# ESP32.net
KiCad netlist of a schematic drawn in Altium Designer
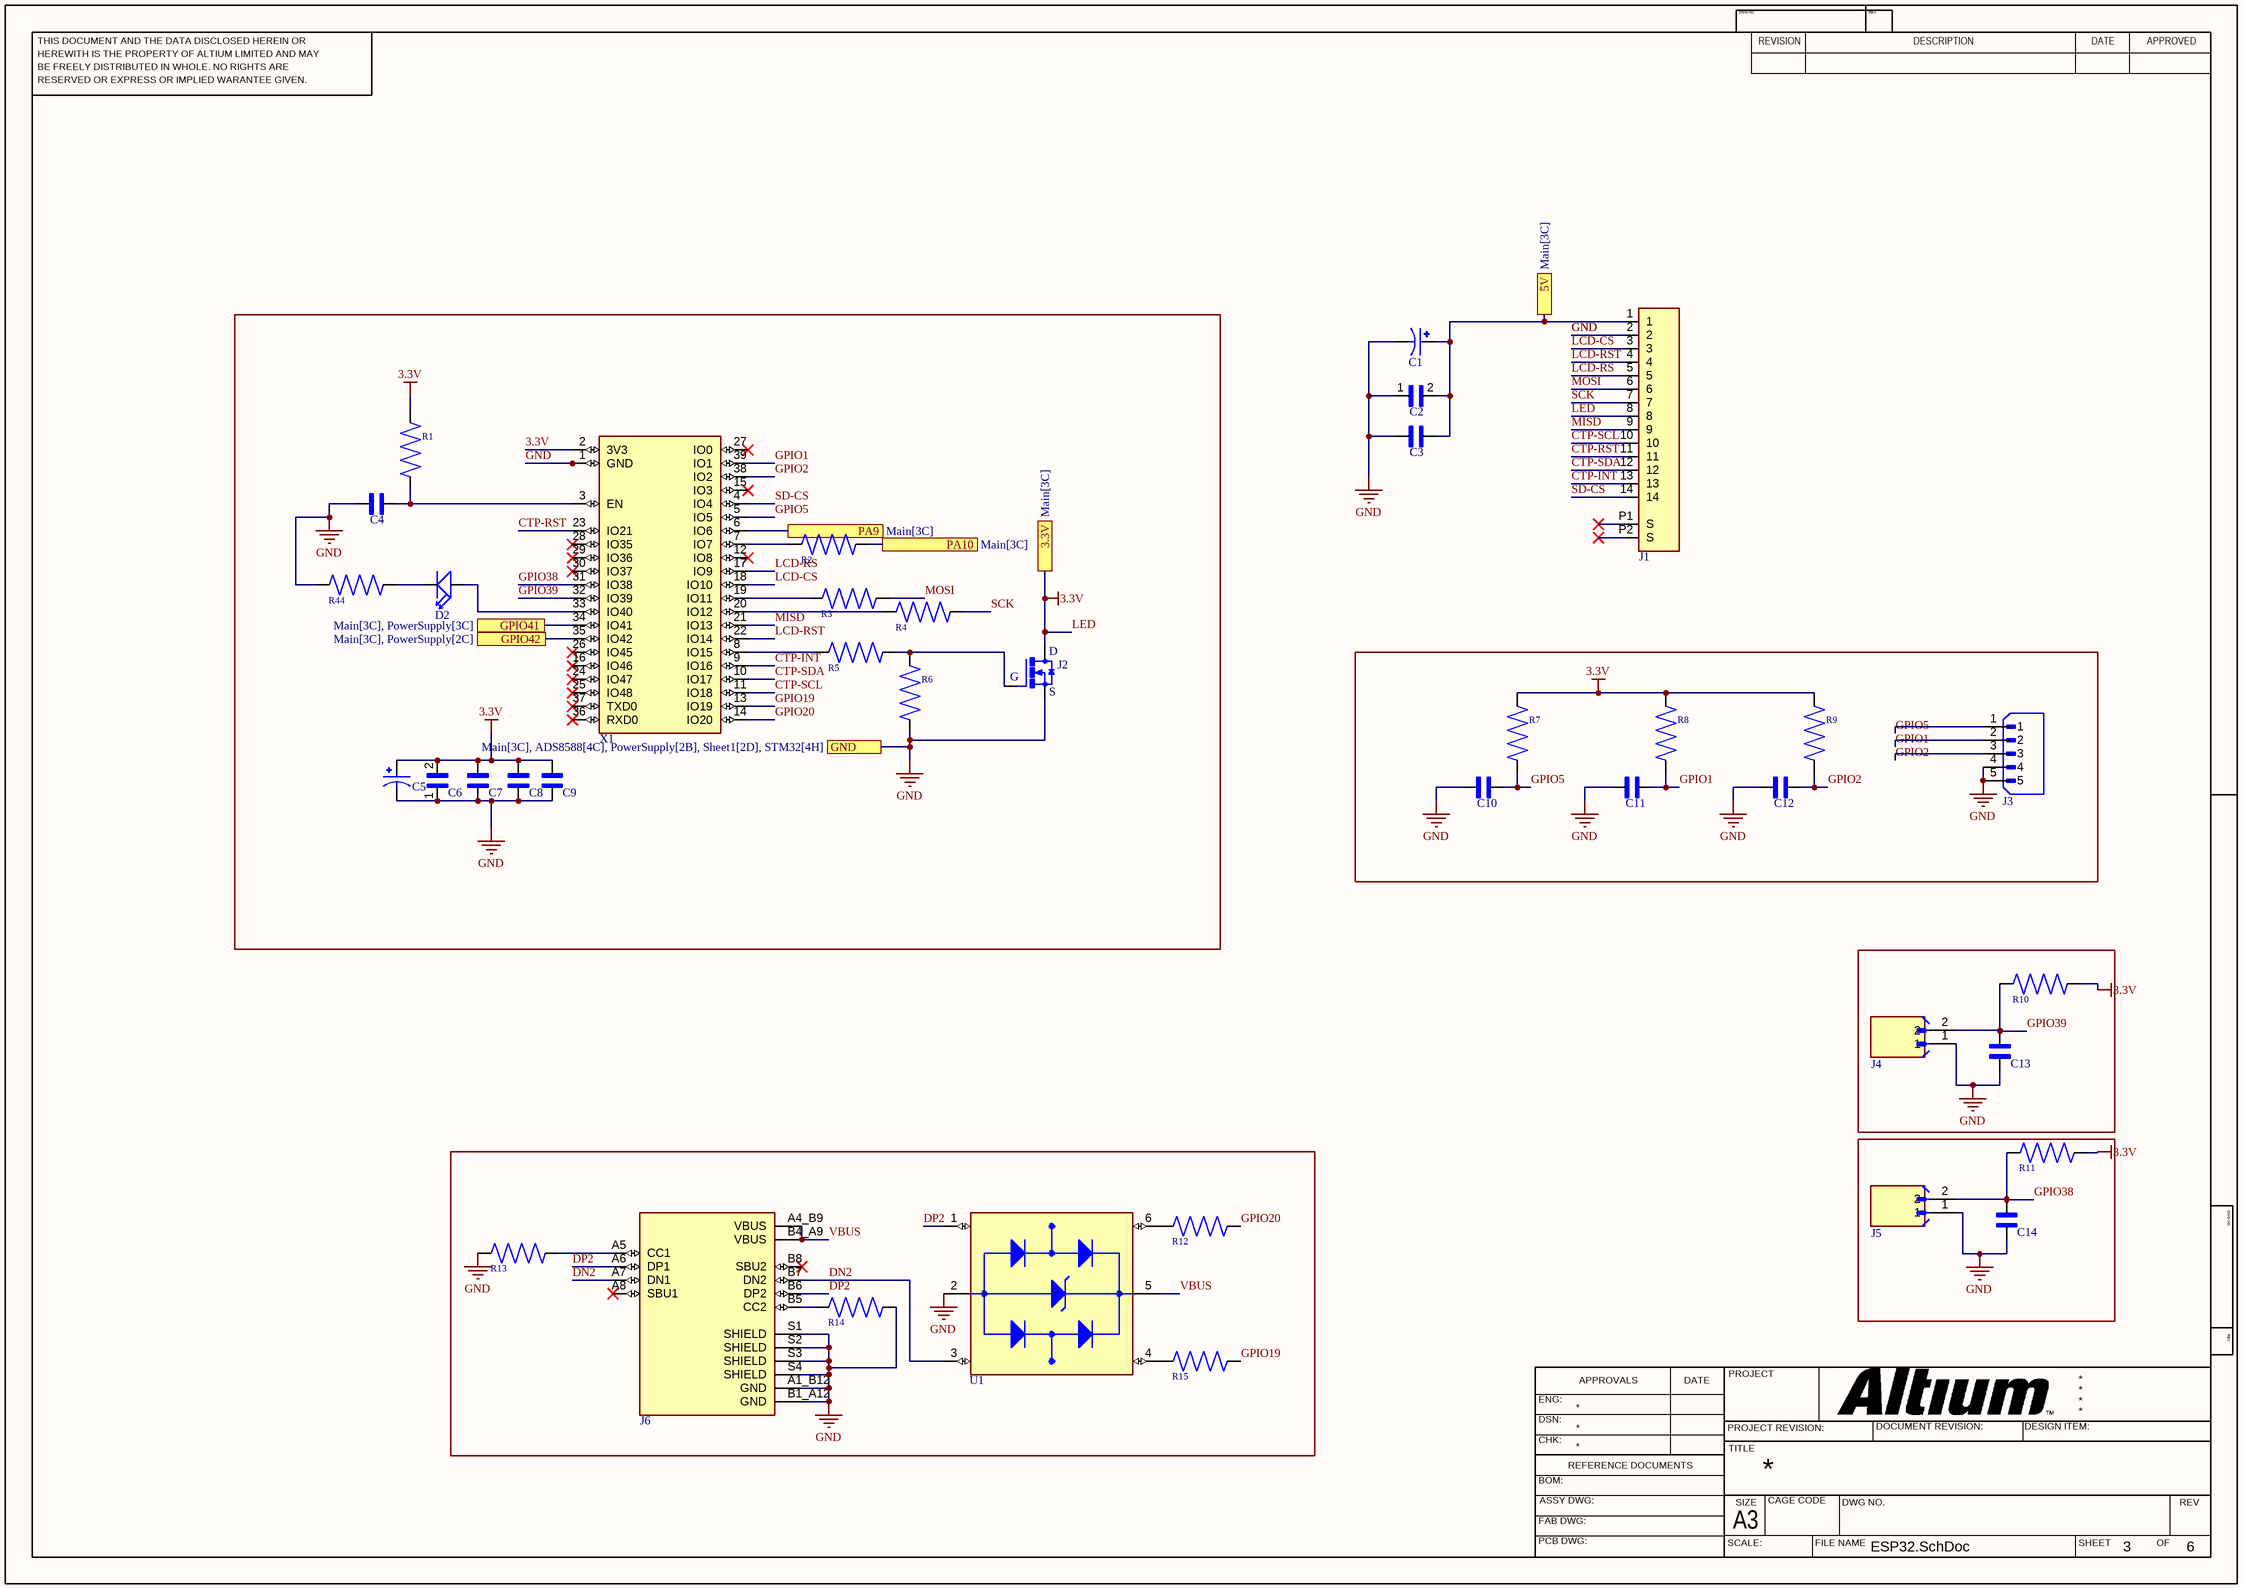
[diagram p0: ESP32.SchDoc]

(export (version "E")
  (design (tool "Eeschema 10.0.6"))
  (components
    (comp (ref "C1")
      (value "100 uF")
      (footprint "100 uF")
      (fields (field (name "MF") "Panasonic") (field (name "MP") "16SVPG100M"))
      (libsource (lib "") (part "100 uF_1"))
    )
    (comp (ref "C2")
      (value "C2012X7R1H104K085AA")
      (footprint "CAPC2012X100N")
      (description "0.1 ÂµF Â±10% 50V Ceramic Capacitor X7R 0805 (2012 Metric)")
      (fields (field (name "MF") "TDK") (field (name "DIGI-KEY_PART_NUMBER") "445-7534-1-ND"))
      (libsource (lib "ESP32-S3-WROOM-1-N16R8") (part "C2012X7R1H104K085AA"))
    )
    (comp (ref "C3")
      (value "CAP603")
      (footprint "CAP603")
      (description "0.1 ÂµF Â±5% 10V Ceramic Capacitor X7R 0603 (1608 Metric)")
      (fields (field (name "MF") "Vishay") (field (name "MP") "VJ0603Y104JXQCW1BC"))
      (libsource (lib "") (part "CAP603_1"))
    )
    (comp (ref "C4")
      (value "CAP603")
      (footprint "CAP603")
      (description "0.1 ÂµF Â±5% 10V Ceramic Capacitor X7R 0603 (1608 Metric)")
      (fields (field (name "MF") "Vishay") (field (name "MP") "VJ0603Y104JXQCW1BC"))
      (libsource (lib "") (part "CAP603_1"))
    )
    (comp (ref "C5")
      (value "100 uF")
      (footprint "100 uF")
      (fields (field (name "MF") "Panasonic") (field (name "MP") "16SVPG100M"))
      (libsource (lib "ESP32-S3-WROOM-1-N16R8") (part "100 uF"))
    )
    (comp (ref "C6")
      (value "C2012X7R1H104K085AA")
      (footprint "CAPC2012X100N")
      (description "0.1 ÂµF Â±10% 50V Ceramic Capacitor X7R 0805 (2012 Metric)")
      (fields (field (name "MF") "TDK") (field (name "DIGI-KEY_PART_NUMBER") "445-7534-1-ND"))
      (libsource (lib "") (part "C2012X7R1H104K085AA_1"))
    )
    (comp (ref "C7")
      (value "CAP603")
      (footprint "CAP603")
      (description "0.1 ÂµF Â±5% 10V Ceramic Capacitor X7R 0603 (1608 Metric)")
      (fields (field (name "MF") "Vishay") (field (name "MP") "VJ0603Y104JXQCW1BC"))
      (libsource (lib "ESP32-S3-WROOM-1-N16R8") (part "CAP603"))
    )
    (comp (ref "C8")
      (value "CAP603")
      (footprint "CAP603")
      (description "0.1 ÂµF Â±5% 10V Ceramic Capacitor X7R 0603 (1608 Metric)")
      (fields (field (name "MF") "Vishay") (field (name "MP") "VJ0603Y104JXQCW1BC"))
      (libsource (lib "ESP32-S3-WROOM-1-N16R8") (part "CAP603"))
    )
    (comp (ref "C9")
      (value "CAP603")
      (footprint "CAP603")
      (description "0.1 ÂµF Â±5% 10V Ceramic Capacitor X7R 0603 (1608 Metric)")
      (fields (field (name "MF") "Vishay") (field (name "MP") "VJ0603Y104JXQCW1BC"))
      (libsource (lib "ESP32-S3-WROOM-1-N16R8") (part "CAP603"))
    )
    (comp (ref "C10")
      (value "CAP603")
      (footprint "CAP603")
      (description "0.1 ÂµF Â±5% 10V Ceramic Capacitor X7R 0603 (1608 Metric)")
      (fields (field (name "MF") "Vishay") (field (name "MP") "VJ0603Y104JXQCW1BC"))
      (libsource (lib "") (part "CAP603_1"))
    )
    (comp (ref "C11")
      (value "CAP603")
      (footprint "CAP603")
      (description "0.1 ÂµF Â±5% 10V Ceramic Capacitor X7R 0603 (1608 Metric)")
      (fields (field (name "MF") "Vishay") (field (name "MP") "VJ0603Y104JXQCW1BC"))
      (libsource (lib "") (part "CAP603_1"))
    )
    (comp (ref "C12")
      (value "CAP603")
      (footprint "CAP603")
      (description "0.1 ÂµF Â±5% 10V Ceramic Capacitor X7R 0603 (1608 Metric)")
      (fields (field (name "MF") "Vishay") (field (name "MP") "VJ0603Y104JXQCW1BC"))
      (libsource (lib "") (part "CAP603_1"))
    )
    (comp (ref "C13")
      (value "CAP603")
      (footprint "CAP603")
      (description "0.1 ÂµF Â±5% 10V Ceramic Capacitor X7R 0603 (1608 Metric)")
      (fields (field (name "MF") "Vishay") (field (name "MP") "VJ0603Y104JXQCW1BC"))
      (libsource (lib "ESP32-S3-WROOM-1-N16R8") (part "CAP603"))
    )
    (comp (ref "C14")
      (value "CAP603")
      (footprint "CAP603")
      (description "0.1 ÂµF Â±5% 10V Ceramic Capacitor X7R 0603 (1608 Metric)")
      (fields (field (name "MF") "Vishay") (field (name "MP") "VJ0603Y104JXQCW1BC"))
      (libsource (lib "ESP32-S3-WROOM-1-N16R8") (part "CAP603"))
    )
    (comp (ref "D2")
      (value "SMD-LED-YELLOW-WHITE(0603)")
      (footprint "LED-0603")
      (description "SMD LED Yellow-White")
      (fields (field (name "MF") "Chengguangxing") (field (name "MP") "ADL-0603W"))
      (libsource (lib "ESP32-S3-WROOM-1-N16R8") (part "SMD-LED-YELLOW-WHITE(0603)"))
    )
    (comp (ref "J1")
      (value "FPC-connector")
      (footprint "FPC-connector")
      (description "14 Position FPC Connector Contacts, Top 0.020 (0.50mm) Surface Mount, Right Angle")
      (fields (field (name "MF") "TE Connectivity") (field (name "MP") "1-1734839-4"))
      (libsource (lib "ESP32-S3-WROOM-1-N16R8") (part "FPC-connector"))
    )
    (comp (ref "J2")
      (value "AO3400")
      (footprint "AO3400")
      (description "N-Channel 30 V 5.8A (Ta) 1.4W (Ta) Surface Mount SOT-23-3")
      (fields (field (name "MF") "Alpha &"))
      (libsource (lib "ESP32-S3-WROOM-1-N16R8") (part "AO3400"))
    )
    (comp (ref "J3")
      (value "5-pin jst")
      (footprint "5-pin jst")
      (description "Connector Header Through Hole 5 position 0.098 (2.50mm)")
      (fields (field (name "MF") "JST Sales America Inc.") (field (name "MP") "B5B-XH-A(LF)(SN)"))
      (libsource (lib "ESP32-S3-WROOM-1-N16R8") (part "5-pin jst"))
    )
    (comp (ref "J4")
      (value "2-pin jst")
      (footprint "2-pin jst")
      (description "Connector Header Through Hole 2 position 0.079 (2.00mm)")
      (fields (field (name "MF") "JST Sales America Inc.") (field (name "MP") "B2B-PH-K-S"))
      (libsource (lib "ESP32-S3-WROOM-1-N16R8") (part "2-pin jst"))
    )
    (comp (ref "J5")
      (value "2-pin jst")
      (footprint "2-pin jst")
      (description "Connector Header Through Hole 2 position 0.079 (2.00mm)")
      (fields (field (name "MF") "JST Sales America Inc.") (field (name "MP") "B2B-PH-K-S"))
      (libsource (lib "ESP32-S3-WROOM-1-N16R8") (part "2-pin jst"))
    )
    (comp (ref "J6")
      (value "TYPE-C-31-M-12")
      (footprint "TYPE-C-31-M-12")
      (description "USB Connectors 24 Receptacle 1 8.94*7.3mm RoHS")
      (fields (field (name "MF") "HRO Electronics Co., Ltd."))
      (libsource (lib "ESP32-S3-WROOM-1-N16R8") (part "TYPE-C-31-M-12"))
    )
    (comp (ref "R1")
      (value "RES-603")
      (footprint "CAP603")
      (fields (field (name "MF") "Yageo") (field (name "MP") "RC0805FR-0710KL"))
      (libsource (lib "ESP32-S3-WROOM-1-N16R8") (part "RES-603"))
    )
    (comp (ref "R2")
      (value "RES-603")
      (footprint "CAP603")
      (fields (field (name "MF") "Yageo") (field (name "MP") "RC0805FR-0710KL"))
      (libsource (lib "ESP32-S3-WROOM-1-N16R8") (part "RES-603"))
    )
    (comp (ref "R3")
      (value "RES-603")
      (footprint "CAP603")
      (fields (field (name "MF") "Yageo") (field (name "MP") "RC0805FR-0710KL"))
      (libsource (lib "ESP32-S3-WROOM-1-N16R8") (part "RES-603"))
    )
    (comp (ref "R4")
      (value "RES-603")
      (footprint "CAP603")
      (fields (field (name "MF") "Yageo") (field (name "MP") "RC0805FR-0710KL"))
      (libsource (lib "ESP32-S3-WROOM-1-N16R8") (part "RES-603"))
    )
    (comp (ref "R5")
      (value "RES-603")
      (footprint "CAP603")
      (fields (field (name "MF") "Yageo") (field (name "MP") "RC0805FR-0710KL"))
      (libsource (lib "ESP32-S3-WROOM-1-N16R8") (part "RES-603"))
    )
    (comp (ref "R6")
      (value "RES-603")
      (footprint "CAP603")
      (fields (field (name "MF") "Yageo") (field (name "MP") "RC0805FR-0710KL"))
      (libsource (lib "ESP32-S3-WROOM-1-N16R8") (part "RES-603"))
    )
    (comp (ref "R7")
      (value "RES-603")
      (footprint "CAP603")
      (fields (field (name "MF") "Yageo") (field (name "MP") "RC0805FR-0710KL"))
      (libsource (lib "ESP32-S3-WROOM-1-N16R8") (part "RES-603"))
    )
    (comp (ref "R8")
      (value "RES-603")
      (footprint "CAP603")
      (fields (field (name "MF") "Yageo") (field (name "MP") "RC0805FR-0710KL"))
      (libsource (lib "ESP32-S3-WROOM-1-N16R8") (part "RES-603"))
    )
    (comp (ref "R9")
      (value "RES-603")
      (footprint "CAP603")
      (fields (field (name "MF") "Yageo") (field (name "MP") "RC0805FR-0710KL"))
      (libsource (lib "ESP32-S3-WROOM-1-N16R8") (part "RES-603"))
    )
    (comp (ref "R10")
      (value "RES-603")
      (footprint "CAP603")
      (fields (field (name "MF") "Yageo") (field (name "MP") "RC0805FR-0710KL"))
      (libsource (lib "ESP32-S3-WROOM-1-N16R8") (part "RES-603"))
    )
    (comp (ref "R11")
      (value "RES-603")
      (footprint "CAP603")
      (fields (field (name "MF") "Yageo") (field (name "MP") "RC0805FR-0710KL"))
      (libsource (lib "ESP32-S3-WROOM-1-N16R8") (part "RES-603"))
    )
    (comp (ref "R12")
      (value "RES-603")
      (footprint "CAP603")
      (fields (field (name "MF") "Yageo") (field (name "MP") "RC0805FR-0710KL"))
      (libsource (lib "ESP32-S3-WROOM-1-N16R8") (part "RES-603"))
    )
    (comp (ref "R13")
      (value "RES-603")
      (footprint "CAP603")
      (fields (field (name "MF") "Yageo") (field (name "MP") "RC0805FR-0710KL"))
      (libsource (lib "ESP32-S3-WROOM-1-N16R8") (part "RES-603"))
    )
    (comp (ref "R14")
      (value "RES-603")
      (footprint "CAP603")
      (fields (field (name "MF") "Yageo") (field (name "MP") "RC0805FR-0710KL"))
      (libsource (lib "ESP32-S3-WROOM-1-N16R8") (part "RES-603"))
    )
    (comp (ref "R15")
      (value "RES-603")
      (footprint "CAP603")
      (fields (field (name "MF") "Yageo") (field (name "MP") "RC0805FR-0710KL"))
      (libsource (lib "ESP32-S3-WROOM-1-N16R8") (part "RES-603"))
    )
    (comp (ref "R44")
      (value "RES-603")
      (footprint "CAP603")
      (fields (field (name "MF") "Yageo") (field (name "MP") "RC0805FR-0710KL"))
      (libsource (lib "ESP32-S3-WROOM-1-N16R8") (part "RES-603"))
    )
    (comp (ref "U1")
      (value "USBLC6-2SC6")
      (footprint "USBLC6-2SC6")
      (description "17V Clamp 5A (8/20Âµs) Ipp Tvs Diode Surface Mount SOT-23-6")
      (fields (field (name "MF") "STMicroelectronics"))
      (libsource (lib "ESP32-S3-WROOM-1-N16R8") (part "USBLC6-2SC6"))
    )
    (comp (ref "X1")
      (value "ESP32-S3-WROOM-1-N16R8")
      (footprint "ESP32S3WROOM1N8R2")
      (description "Bluetooth, WiFi 802.11b/g/n, Bluetooth v5.0 Transceiver Module 2.4GHz PCB Trace Surface Mount")
      (fields (field (name "MF") "Espressif Systems"))
      (libsource (lib "ESP32-S3-WROOM-1-N16R8") (part "ESP32-S3-WROOM-1-N16R8"))
    )
  )
  (nets
    (net (code "1") (name "/5V") (class "Default")
      (node (ref "C1") (pin "1") (pinfunction "1_1") (pintype "passive"))
      (node (ref "C2") (pin "2") (pinfunction "2_2") (pintype "passive"))
      (node (ref "C3") (pin "1") (pinfunction "1_1") (pintype "passive"))
      (node (ref "J1") (pin "1") (pinfunction "1_1") (pintype "passive"))
    )
    (net (code "2") (name "/CTP-INT") (class "Default")
      (node (ref "J1") (pin "13") (pinfunction "13_13") (pintype "passive"))
      (node (ref "X1") (pin "9") (pinfunction "IO16_9") (pintype "bidirectional"))
    )
    (net (code "3") (name "/CTP-RST") (class "Default")
      (node (ref "J1") (pin "11") (pinfunction "11_11") (pintype "passive"))
      (node (ref "X1") (pin "23") (pinfunction "IO21_23") (pintype "bidirectional"))
    )
    (net (code "4") (name "/CTP-SCL") (class "Default")
      (node (ref "J1") (pin "10") (pinfunction "10_10") (pintype "passive"))
      (node (ref "X1") (pin "11") (pinfunction "IO18_11") (pintype "bidirectional"))
    )
    (net (code "5") (name "/CTP-SDA") (class "Default")
      (node (ref "J1") (pin "12") (pinfunction "12_12") (pintype "passive"))
      (node (ref "X1") (pin "10") (pinfunction "IO17_10") (pintype "bidirectional"))
    )
    (net (code "6") (name "/DN2") (class "Default")
      (node (ref "J6") (pin "A7") (pinfunction "DN1_A7") (pintype "bidirectional"))
      (node (ref "J6") (pin "B7") (pinfunction "DN2_B7") (pintype "bidirectional"))
      (node (ref "U1") (pin "3") (pinfunction "I/O2_IN_3") (pintype "bidirectional"))
    )
    (net (code "7") (name "/DP2") (class "Default")
      (node (ref "J6") (pin "A6") (pinfunction "DP1_A6") (pintype "bidirectional"))
      (node (ref "J6") (pin "B6") (pinfunction "DP2_B6") (pintype "bidirectional"))
      (node (ref "U1") (pin "1") (pinfunction "I/O1_IN_1") (pintype "bidirectional"))
    )
    (net (code "8") (name "/GPIO1") (class "Default")
      (node (ref "C11") (pin "1") (pinfunction "1_1") (pintype "passive"))
      (node (ref "J3") (pin "2") (pinfunction "2_2") (pintype "passive"))
      (node (ref "R8") (pin "1") (pinfunction "1_1") (pintype "passive"))
      (node (ref "X1") (pin "39") (pinfunction "IO1_39") (pintype "bidirectional"))
    )
    (net (code "9") (name "/GPIO2") (class "Default")
      (node (ref "C12") (pin "1") (pinfunction "1_1") (pintype "passive"))
      (node (ref "J3") (pin "3") (pinfunction "3_3") (pintype "passive"))
      (node (ref "R9") (pin "1") (pinfunction "1_1") (pintype "passive"))
      (node (ref "X1") (pin "38") (pinfunction "IO2_38") (pintype "bidirectional"))
    )
    (net (code "10") (name "/GPIO5") (class "Default")
      (node (ref "C10") (pin "1") (pinfunction "1_1") (pintype "passive"))
      (node (ref "J3") (pin "1") (pinfunction "1_1") (pintype "passive"))
      (node (ref "R7") (pin "1") (pinfunction "1_1") (pintype "passive"))
      (node (ref "X1") (pin "5") (pinfunction "IO5_5") (pintype "bidirectional"))
    )
    (net (code "11") (name "/GPIO19") (class "Default")
      (node (ref "R15") (pin "1") (pinfunction "1_1") (pintype "passive"))
      (node (ref "X1") (pin "13") (pinfunction "IO19_13") (pintype "bidirectional"))
    )
    (net (code "12") (name "/GPIO20") (class "Default")
      (node (ref "R12") (pin "1") (pinfunction "1_1") (pintype "passive"))
      (node (ref "X1") (pin "14") (pinfunction "IO20_14") (pintype "bidirectional"))
    )
    (net (code "13") (name "/GPIO38") (class "Default")
      (node (ref "C14") (pin "2") (pinfunction "2_2") (pintype "passive"))
      (node (ref "J5") (pin "2") (pinfunction "2_2") (pintype "passive"))
      (node (ref "R11") (pin "2") (pinfunction "2_2") (pintype "passive"))
      (node (ref "X1") (pin "31") (pinfunction "IO38_31") (pintype "bidirectional"))
    )
    (net (code "14") (name "/GPIO39") (class "Default")
      (node (ref "C13") (pin "2") (pinfunction "2_2") (pintype "passive"))
      (node (ref "J4") (pin "2") (pinfunction "2_2") (pintype "passive"))
      (node (ref "R10") (pin "2") (pinfunction "2_2") (pintype "passive"))
      (node (ref "X1") (pin "32") (pinfunction "IO39_32") (pintype "bidirectional"))
    )
    (net (code "15") (name "/GPIO41") (class "Default")
      (node (ref "X1") (pin "34") (pinfunction "IO41_34") (pintype "bidirectional"))
    )
    (net (code "16") (name "/GPIO42") (class "Default")
      (node (ref "X1") (pin "35") (pinfunction "IO42_35") (pintype "bidirectional"))
    )
    (net (code "17") (name "/LCD-CS") (class "Default")
      (node (ref "J1") (pin "3") (pinfunction "3_3") (pintype "passive"))
      (node (ref "X1") (pin "18") (pinfunction "IO10_18") (pintype "bidirectional"))
    )
    (net (code "18") (name "/LCD-RS") (class "Default")
      (node (ref "J1") (pin "5") (pinfunction "5_5") (pintype "passive"))
      (node (ref "X1") (pin "17") (pinfunction "IO9_17") (pintype "bidirectional"))
    )
    (net (code "19") (name "/LCD-RST") (class "Default")
      (node (ref "J1") (pin "4") (pinfunction "4_4") (pintype "passive"))
      (node (ref "X1") (pin "22") (pinfunction "IO14_22") (pintype "bidirectional"))
    )
    (net (code "20") (name "/MISD") (class "Default")
      (node (ref "J1") (pin "9") (pinfunction "9_9") (pintype "passive"))
      (node (ref "X1") (pin "21") (pinfunction "IO13_21") (pintype "bidirectional"))
    )
    (net (code "21") (name "/MOSI") (class "Default")
      (node (ref "J1") (pin "6") (pinfunction "6_6") (pintype "passive"))
      (node (ref "R3") (pin "1") (pinfunction "1_1") (pintype "passive"))
    )
    (net (code "22") (name "/PA9") (class "Default")
      (node (ref "X1") (pin "6") (pinfunction "IO6_6") (pintype "bidirectional"))
    )
    (net (code "23") (name "/PA10") (class "Default")
      (node (ref "R2") (pin "1") (pinfunction "1_1") (pintype "passive"))
    )
    (net (code "24") (name "/SCK") (class "Default")
      (node (ref "J1") (pin "7") (pinfunction "7_7") (pintype "passive"))
      (node (ref "R4") (pin "1") (pinfunction "1_1") (pintype "passive"))
    )
    (net (code "25") (name "/SD-CS") (class "Default")
      (node (ref "J1") (pin "14") (pinfunction "14_14") (pintype "passive"))
      (node (ref "X1") (pin "4") (pinfunction "IO4_4") (pintype "bidirectional"))
    )
    (net (code "26") (name "/VBUS") (class "Default")
      (node (ref "J6") (pin "A4_B9") (pinfunction "VBUS_A4_B9") (pintype "power_in"))
      (node (ref "J6") (pin "B4_A9") (pinfunction "VBUS_B4_A9") (pintype "power_in"))
      (node (ref "U1") (pin "5") (pinfunction "VBUS_5") (pintype "power_in"))
    )
    (net (code "27") (name "3.3V") (class "Default")
      (node (ref "C5") (pin "1") (pinfunction "1_1") (pintype "passive"))
      (node (ref "C6") (pin "2") (pinfunction "2_2") (pintype "passive"))
      (node (ref "C7") (pin "2") (pinfunction "2_2") (pintype "passive"))
      (node (ref "C8") (pin "2") (pinfunction "2_2") (pintype "passive"))
      (node (ref "C9") (pin "2") (pinfunction "2_2") (pintype "passive"))
      (node (ref "J1") (pin "8") (pinfunction "8_8") (pintype "passive"))
      (node (ref "J2") (pin "3") (pinfunction "D_3") (pintype "passive"))
      (node (ref "R1") (pin "2") (pinfunction "2_2") (pintype "passive"))
      (node (ref "R10") (pin "1") (pinfunction "1_1") (pintype "passive"))
      (node (ref "R11") (pin "1") (pinfunction "1_1") (pintype "passive"))
      (node (ref "R7") (pin "2") (pinfunction "2_2") (pintype "passive"))
      (node (ref "R8") (pin "2") (pinfunction "2_2") (pintype "passive"))
      (node (ref "R9") (pin "2") (pinfunction "2_2") (pintype "passive"))
      (node (ref "X1") (pin "2") (pinfunction "3V3_2") (pintype "bidirectional"))
    )
    (net (code "28") (name "GND") (class "Default")
      (node (ref "C1") (pin "2") (pinfunction "2_2") (pintype "passive"))
      (node (ref "C10") (pin "2") (pinfunction "2_2") (pintype "passive"))
      (node (ref "C11") (pin "2") (pinfunction "2_2") (pintype "passive"))
      (node (ref "C12") (pin "2") (pinfunction "2_2") (pintype "passive"))
      (node (ref "C13") (pin "1") (pinfunction "1_1") (pintype "passive"))
      (node (ref "C14") (pin "1") (pinfunction "1_1") (pintype "passive"))
      (node (ref "C2") (pin "1") (pinfunction "1_1") (pintype "passive"))
      (node (ref "C3") (pin "2") (pinfunction "2_2") (pintype "passive"))
      (node (ref "C4") (pin "2") (pinfunction "2_2") (pintype "passive"))
      (node (ref "C5") (pin "2") (pinfunction "2_2") (pintype "passive"))
      (node (ref "C6") (pin "1") (pinfunction "1_1") (pintype "passive"))
      (node (ref "C7") (pin "1") (pinfunction "1_1") (pintype "passive"))
      (node (ref "C8") (pin "1") (pinfunction "1_1") (pintype "passive"))
      (node (ref "C9") (pin "1") (pinfunction "1_1") (pintype "passive"))
      (node (ref "J1") (pin "2") (pinfunction "2_2") (pintype "passive"))
      (node (ref "J2") (pin "2") (pinfunction "S_2") (pintype "passive"))
      (node (ref "J3") (pin "4") (pinfunction "4_4") (pintype "passive"))
      (node (ref "J3") (pin "5") (pinfunction "5_5") (pintype "passive"))
      (node (ref "J4") (pin "1") (pinfunction "1_1") (pintype "passive"))
      (node (ref "J5") (pin "1") (pinfunction "1_1") (pintype "passive"))
      (node (ref "J6") (pin "A1_B12") (pinfunction "GND_A1_B12") (pintype "passive"))
      (node (ref "J6") (pin "B1_A12") (pinfunction "GND_B1_A12") (pintype "passive"))
      (node (ref "J6") (pin "S1") (pinfunction "SHIELD_S1") (pintype "passive"))
      (node (ref "J6") (pin "S2") (pinfunction "SHIELD_S2") (pintype "passive"))
      (node (ref "J6") (pin "S3") (pinfunction "SHIELD_S3") (pintype "passive"))
      (node (ref "J6") (pin "S4") (pinfunction "SHIELD_S4") (pintype "passive"))
      (node (ref "R13") (pin "2") (pinfunction "2_2") (pintype "passive"))
      (node (ref "R14") (pin "1") (pinfunction "1_1") (pintype "passive"))
      (node (ref "R44") (pin "1") (pinfunction "1_1") (pintype "passive"))
      (node (ref "R6") (pin "1") (pinfunction "1_1") (pintype "passive"))
      (node (ref "U1") (pin "2") (pinfunction "GND_2") (pintype "power_in"))
      (node (ref "X1") (pin "1") (pinfunction "GND_1") (pintype "bidirectional"))
      (node (ref "X1") (pin "40") (pinfunction "GND_40") (pintype "bidirectional"))
      (node (ref "X1") (pin "41") (pinfunction "GND_41") (pintype "bidirectional"))
      (node (ref "X1") (pin "42") (pinfunction "GND_42") (pintype "bidirectional"))
      (node (ref "X1") (pin "43") (pinfunction "GND_43") (pintype "bidirectional"))
      (node (ref "X1") (pin "44") (pinfunction "GND_44") (pintype "bidirectional"))
      (node (ref "X1") (pin "45") (pinfunction "GND_45") (pintype "bidirectional"))
      (node (ref "X1") (pin "46") (pinfunction "GND_46") (pintype "bidirectional"))
      (node (ref "X1") (pin "47") (pinfunction "GND_47") (pintype "bidirectional"))
      (node (ref "X1") (pin "48") (pinfunction "GND_48") (pintype "bidirectional"))
      (node (ref "X1") (pin "49") (pinfunction "GND_49") (pintype "bidirectional"))
    )
    (net (code "29") (name "Net-(D2-PadNEG)") (class "Default")
      (node (ref "D2") (pin "NEG") (pinfunction "NEG_NEG") (pintype "passive"))
      (node (ref "R44") (pin "2") (pinfunction "2_2") (pintype "passive"))
    )
    (net (code "30") (name "Net-(J2-G)") (class "Default")
      (node (ref "J2") (pin "1") (pinfunction "G_1") (pintype "passive"))
      (node (ref "R5") (pin "1") (pinfunction "1_1") (pintype "passive"))
      (node (ref "R6") (pin "2") (pinfunction "2_2") (pintype "passive"))
    )
    (net (code "31") (name "Net-(J6-CC1)") (class "Default")
      (node (ref "J6") (pin "A5") (pinfunction "CC1_A5") (pintype "bidirectional"))
      (node (ref "R13") (pin "1") (pinfunction "1_1") (pintype "passive"))
    )
    (net (code "32") (name "Net-(J6-CC2)") (class "Default")
      (node (ref "J6") (pin "B5") (pinfunction "CC2_B5") (pintype "bidirectional"))
      (node (ref "R14") (pin "2") (pinfunction "2_2") (pintype "passive"))
    )
    (net (code "33") (name "Net-(U1-I{slash}O1_OUT)") (class "Default")
      (node (ref "R12") (pin "2") (pinfunction "2_2") (pintype "passive"))
      (node (ref "U1") (pin "6") (pinfunction "I/O1_OUT_6") (pintype "bidirectional"))
    )
    (net (code "34") (name "Net-(U1-I{slash}O2_OUT)") (class "Default")
      (node (ref "R15") (pin "2") (pinfunction "2_2") (pintype "passive"))
      (node (ref "U1") (pin "4") (pinfunction "I/O2_OUT_4") (pintype "bidirectional"))
    )
    (net (code "35") (name "Net-(X1-EN)") (class "Default")
      (node (ref "C4") (pin "1") (pinfunction "1_1") (pintype "passive"))
      (node (ref "R1") (pin "1") (pinfunction "1_1") (pintype "passive"))
      (node (ref "X1") (pin "3") (pinfunction "EN_3") (pintype "bidirectional"))
    )
    (net (code "36") (name "Net-(X1-IO7)") (class "Default")
      (node (ref "R2") (pin "2") (pinfunction "2_2") (pintype "passive"))
      (node (ref "X1") (pin "7") (pinfunction "IO7_7") (pintype "bidirectional"))
    )
    (net (code "37") (name "Net-(X1-IO11)") (class "Default")
      (node (ref "R3") (pin "2") (pinfunction "2_2") (pintype "passive"))
      (node (ref "X1") (pin "19") (pinfunction "IO11_19") (pintype "bidirectional"))
    )
    (net (code "38") (name "Net-(X1-IO12)") (class "Default")
      (node (ref "R4") (pin "2") (pinfunction "2_2") (pintype "passive"))
      (node (ref "X1") (pin "20") (pinfunction "IO12_20") (pintype "bidirectional"))
    )
    (net (code "39") (name "Net-(X1-IO15)") (class "Default")
      (node (ref "R5") (pin "2") (pinfunction "2_2") (pintype "passive"))
      (node (ref "X1") (pin "8") (pinfunction "IO15_8") (pintype "bidirectional"))
    )
    (net (code "40") (name "Net-(X1-IO40)") (class "Default")
      (node (ref "D2") (pin "POS") (pinfunction "POS_POS") (pintype "passive"))
      (node (ref "X1") (pin "33") (pinfunction "IO40_33") (pintype "bidirectional"))
    )
    (net (code "41") (name "unconnected-(J1-S-PadP1)") (class "Default")
      (node (ref "J1") (pin "P1") (pinfunction "S_P1") (pintype "passive+no_connect"))
    )
    (net (code "42") (name "unconnected-(J1-S-PadP2)") (class "Default")
      (node (ref "J1") (pin "P2") (pinfunction "S_P2") (pintype "passive+no_connect"))
    )
    (net (code "43") (name "unconnected-(J6-SBU1-PadA8)") (class "Default")
      (node (ref "J6") (pin "A8") (pinfunction "SBU1_A8") (pintype "bidirectional+no_connect"))
    )
    (net (code "44") (name "unconnected-(J6-SBU2-PadB8)") (class "Default")
      (node (ref "J6") (pin "B8") (pinfunction "SBU2_B8") (pintype "bidirectional+no_connect"))
    )
    (net (code "45") (name "unconnected-(X1-IO0-Pad27)") (class "Default")
      (node (ref "X1") (pin "27") (pinfunction "IO0_27") (pintype "bidirectional+no_connect"))
    )
    (net (code "46") (name "unconnected-(X1-IO3-Pad15)") (class "Default")
      (node (ref "X1") (pin "15") (pinfunction "IO3_15") (pintype "bidirectional+no_connect"))
    )
    (net (code "47") (name "unconnected-(X1-IO8-Pad12)") (class "Default")
      (node (ref "X1") (pin "12") (pinfunction "IO8_12") (pintype "bidirectional+no_connect"))
    )
    (net (code "48") (name "unconnected-(X1-IO35-Pad28)") (class "Default")
      (node (ref "X1") (pin "28") (pinfunction "IO35_28") (pintype "bidirectional+no_connect"))
    )
    (net (code "49") (name "unconnected-(X1-IO36-Pad29)") (class "Default")
      (node (ref "X1") (pin "29") (pinfunction "IO36_29") (pintype "bidirectional+no_connect"))
    )
    (net (code "50") (name "unconnected-(X1-IO37-Pad30)") (class "Default")
      (node (ref "X1") (pin "30") (pinfunction "IO37_30") (pintype "bidirectional+no_connect"))
    )
    (net (code "51") (name "unconnected-(X1-IO45-Pad26)") (class "Default")
      (node (ref "X1") (pin "26") (pinfunction "IO45_26") (pintype "bidirectional+no_connect"))
    )
    (net (code "52") (name "unconnected-(X1-IO46-Pad16)") (class "Default")
      (node (ref "X1") (pin "16") (pinfunction "IO46_16") (pintype "bidirectional+no_connect"))
    )
    (net (code "53") (name "unconnected-(X1-IO47-Pad24)") (class "Default")
      (node (ref "X1") (pin "24") (pinfunction "IO47_24") (pintype "bidirectional+no_connect"))
    )
    (net (code "54") (name "unconnected-(X1-IO48-Pad25)") (class "Default")
      (node (ref "X1") (pin "25") (pinfunction "IO48_25") (pintype "bidirectional+no_connect"))
    )
    (net (code "55") (name "unconnected-(X1-RXD0-Pad36)") (class "Default")
      (node (ref "X1") (pin "36") (pinfunction "RXD0_36") (pintype "bidirectional+no_connect"))
    )
    (net (code "56") (name "unconnected-(X1-TXD0-Pad37)") (class "Default")
      (node (ref "X1") (pin "37") (pinfunction "TXD0_37") (pintype "bidirectional+no_connect"))
    )
  )
)
